# Team_1_board.net
KiCad netlist of a schematic drawn in EAGLE
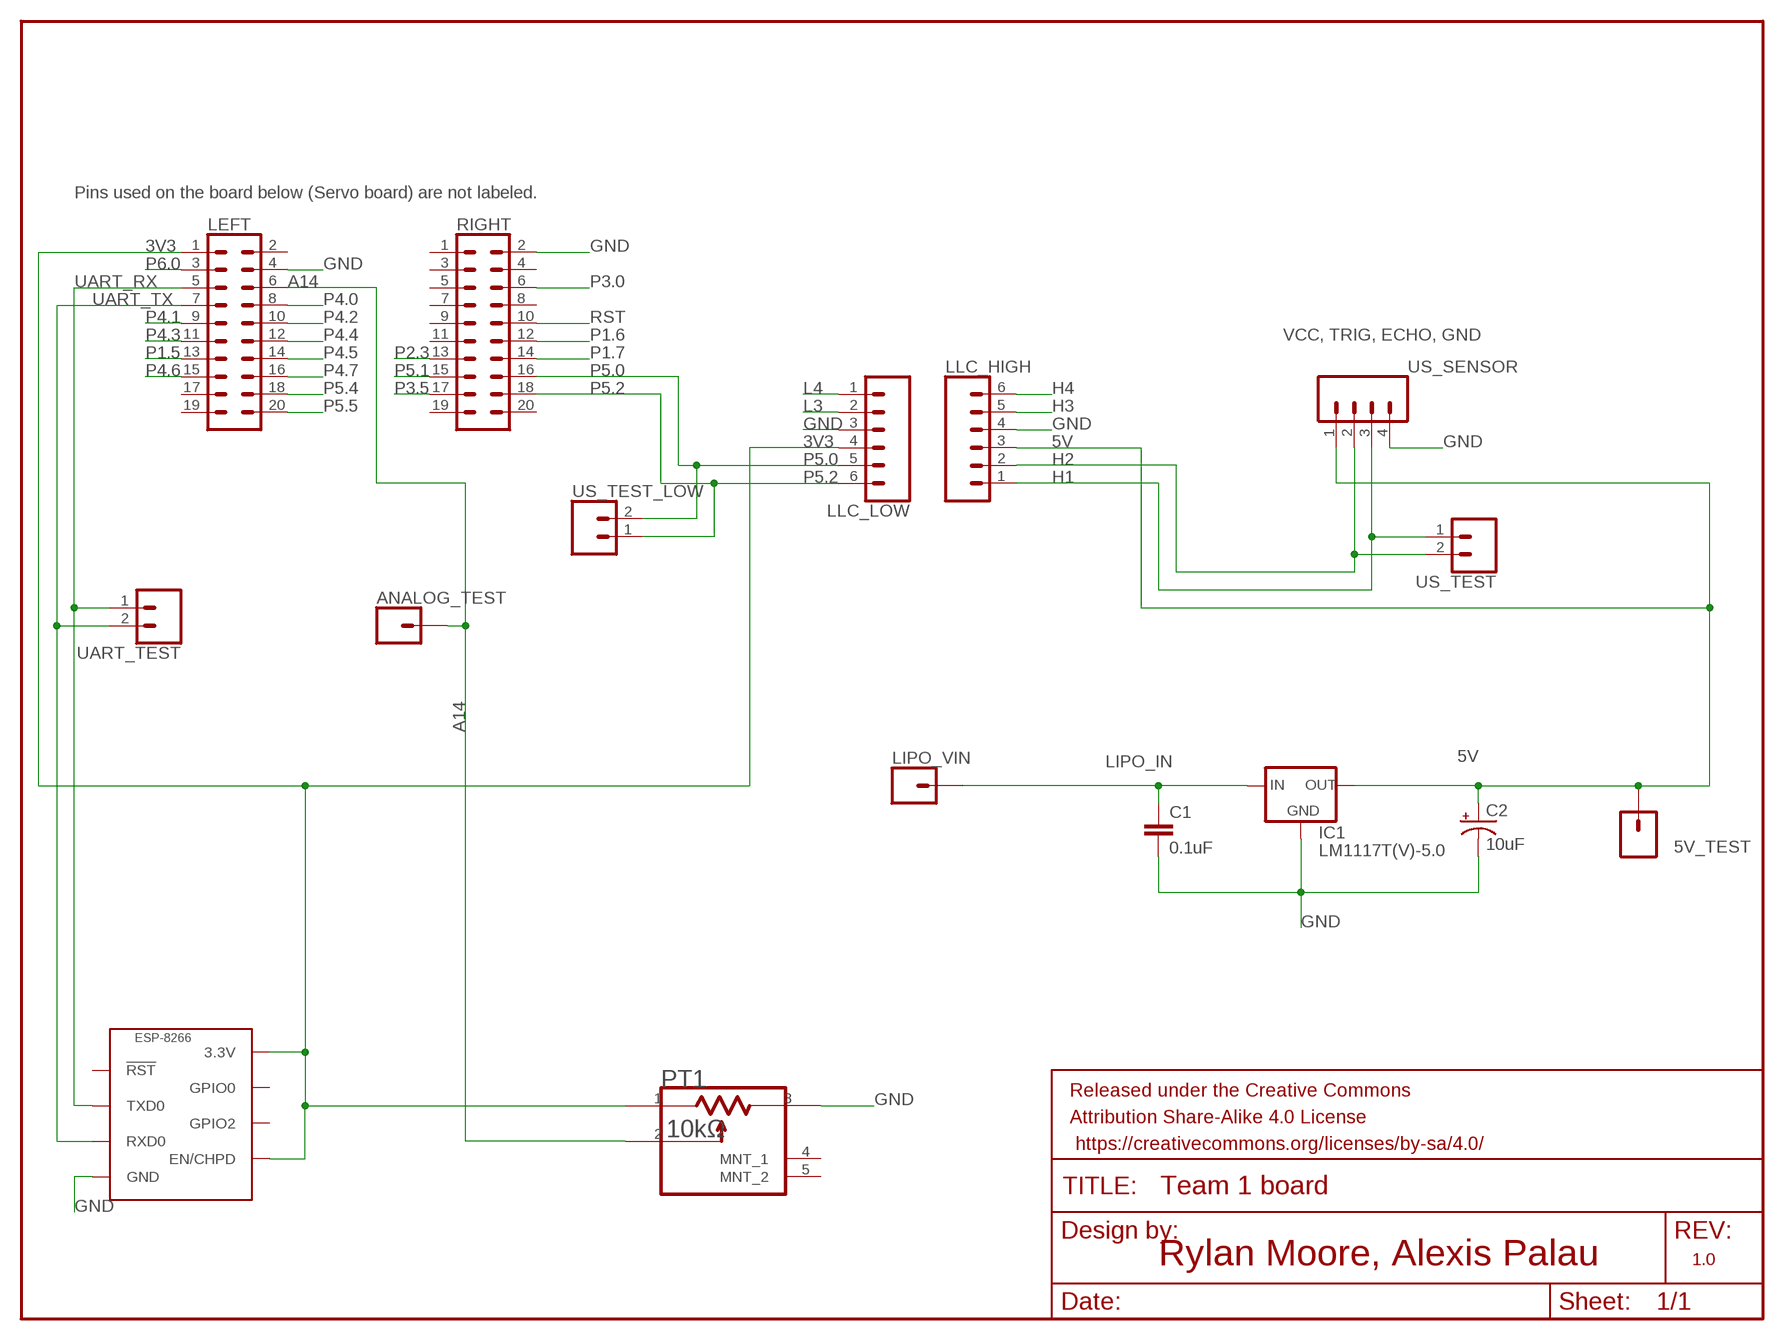
[diagram p0: schematic, sheet 1]

(export (version "E")
  (design (tool "Eeschema 10.0.6"))
  (components
    (comp (ref "5V_TEST")
      (value "CONN_01")
      (footprint "eagle-import:1X01")
      (libsource (lib "eagle-import") (part "CONN_01"))
    )
    (comp (ref "ANALOG_TEST")
      (value "CONN_01")
      (footprint "eagle-import:1X01")
      (libsource (lib "eagle-import") (part "CONN_01"))
    )
    (comp (ref "C1")
      (value "0.1uF")
      (footprint "eagle-import:CAP-PTH-SMALL-KIT")
      (libsource (lib "eagle-import") (part "0.1UF-KIT-EZ-50V-20%"))
    )
    (comp (ref "C2")
      (value "10uF")
      (footprint "eagle-import:CPOL-RADIAL-2.5MM-5MM")
      (libsource (lib "eagle-import") (part "10UF-POLAR-RADIAL-2.5MM-25V-20%"))
    )
    (comp (ref "ESP-8266")
      (value "ESP8266_ESP-01")
      (footprint "eagle-import:ESP8266_ESP-01_NO-SILKSCREEN")
      (libsource (lib "eagle-import") (part "ESP8266_ESP-?01"))
    )
    (comp (ref "FRAME1")
      (value "FRAME-LETTERNO_PACKAGE")
      (footprint "eagle-import:DUMMY")
      (fields (field (name "DESIGNER") "Nobody"))
      (libsource (lib "eagle-import") (part "FRAME-LETTERNO_PACKAGE"))
    )
    (comp (ref "IC1")
      (value "LM1117T(V)-5.0")
      (footprint "eagle-import:TO220V")
      (fields (field (name "MF") "Texas Instruments") (field (name "MPN") "LM1117T-5.0"))
      (libsource (lib "eagle-import") (part "LM1117?-T(V)5.0"))
    )
    (comp (ref "LEFT")
      (value "CONN_10X2NOSILK")
      (footprint "eagle-import:2X10_NOSILK")
      (libsource (lib "eagle-import") (part "CONN_10X2NOSILK"))
    )
    (comp (ref "LIPO_VIN")
      (value "CONN_01")
      (footprint "eagle-import:1X01")
      (libsource (lib "eagle-import") (part "CONN_01"))
    )
    (comp (ref "LLC_HIGH")
      (value "CONN_06SILK_FEMALE_PTH")
      (footprint "eagle-import:1X06")
      (libsource (lib "eagle-import") (part "CONN_06SILK_FEMALE_PTH"))
    )
    (comp (ref "LLC_LOW")
      (value "CONN_06SILK_FEMALE_PTH")
      (footprint "eagle-import:1X06")
      (libsource (lib "eagle-import") (part "CONN_06SILK_FEMALE_PTH"))
    )
    (comp (ref "PT1")
      (value "ECG_EVU-F2AF30B14ECG_EVU-F2AF30B14_0_0")
      (footprint "eagle-import:ECG_EVU-F2AF30B14_0")
      (fields
        (field (name "DIGIKEY_PART_NUMBER") "P3C3103-ND")
        (field (name "MF") "ECG")
        (field (name "MOUSER_PART_NUMBER") "667-EVU-F2AF30B14")
      )
      (libsource (lib "eagle-import") (part "ECG_EVU-F2AF30B14ECG_EVU-F2AF30B14_0_0"))
    )
    (comp (ref "RIGHT")
      (value "CONN_10X2NOSILK")
      (footprint "eagle-import:2X10_NOSILK")
      (libsource (lib "eagle-import") (part "CONN_10X2NOSILK"))
    )
    (comp (ref "UART_TEST")
      (value "CONN_02")
      (footprint "eagle-import:1X02")
      (libsource (lib "eagle-import") (part "CONN_02"))
    )
    (comp (ref "US_SENSOR")
      (value "CONN_04")
      (footprint "eagle-import:1X04")
      (libsource (lib "eagle-import") (part "CONN_04"))
    )
    (comp (ref "US_TEST")
      (value "CONN_02")
      (footprint "eagle-import:1X02")
      (libsource (lib "eagle-import") (part "CONN_02"))
    )
    (comp (ref "US_TEST_LOW")
      (value "CONN_02")
      (footprint "eagle-import:1X02")
      (libsource (lib "eagle-import") (part "CONN_02"))
    )
  )
  (nets
    (net (code "1") (name "/3V3") (class "Default")
      (node (ref "ESP-8266") (pin "3V3") (pinfunction "3.3V_3V3") (pintype "passive"))
      (node (ref "ESP-8266") (pin "EN/CH_PD") (pinfunction "EN/CHPD_EN/CH_PD") (pintype "bidirectional"))
      (node (ref "LEFT") (pin "1") (pinfunction "1_1") (pintype "passive"))
      (node (ref "LLC_LOW") (pin "4") (pinfunction "4_4") (pintype "passive"))
      (node (ref "PT1") (pin "1") (pinfunction "1_1") (pintype "bidirectional"))
    )
    (net (code "2") (name "/5V") (class "Default")
      (node (ref "5V_TEST") (pin "1") (pinfunction "1_1") (pintype "passive"))
      (node (ref "C2") (pin "1") (pinfunction "+_1") (pintype "passive"))
      (node (ref "IC1") (pin "2") (pinfunction "OUT_2") (pintype "passive"))
      (node (ref "LLC_HIGH") (pin "3") (pinfunction "3_3") (pintype "passive"))
      (node (ref "US_SENSOR") (pin "1") (pinfunction "1_1") (pintype "passive"))
    )
    (net (code "3") (name "/A14") (class "Default")
      (node (ref "ANALOG_TEST") (pin "1") (pinfunction "1_1") (pintype "passive"))
      (node (ref "LEFT") (pin "6") (pinfunction "6_6") (pintype "passive"))
      (node (ref "PT1") (pin "2") (pinfunction "2_2") (pintype "bidirectional"))
    )
    (net (code "4") (name "/GND") (class "Default")
      (node (ref "C1") (pin "2") (pinfunction "2_2") (pintype "passive"))
      (node (ref "C2") (pin "2") (pinfunction "-_2") (pintype "passive"))
      (node (ref "ESP-8266") (pin "GND") (pinfunction "GND_GND") (pintype "passive"))
      (node (ref "IC1") (pin "1") (pinfunction "GND_1") (pintype "input"))
      (node (ref "LEFT") (pin "4") (pinfunction "4_4") (pintype "passive"))
      (node (ref "LLC_HIGH") (pin "4") (pinfunction "4_4") (pintype "passive"))
      (node (ref "LLC_LOW") (pin "3") (pinfunction "3_3") (pintype "passive"))
      (node (ref "PT1") (pin "3") (pinfunction "3_3") (pintype "bidirectional"))
      (node (ref "RIGHT") (pin "2") (pinfunction "2_2") (pintype "passive"))
      (node (ref "US_SENSOR") (pin "4") (pinfunction "4_4") (pintype "passive"))
    )
    (net (code "5") (name "/H1") (class "Default")
      (node (ref "LLC_HIGH") (pin "1") (pinfunction "1_1") (pintype "passive"))
      (node (ref "US_SENSOR") (pin "3") (pinfunction "3_3") (pintype "passive"))
      (node (ref "US_TEST") (pin "1") (pinfunction "1_1") (pintype "passive"))
    )
    (net (code "6") (name "/H2") (class "Default")
      (node (ref "LLC_HIGH") (pin "2") (pinfunction "2_2") (pintype "passive"))
      (node (ref "US_SENSOR") (pin "2") (pinfunction "2_2") (pintype "passive"))
      (node (ref "US_TEST") (pin "2") (pinfunction "2_2") (pintype "passive"))
    )
    (net (code "7") (name "/H3") (class "Default")
      (node (ref "LLC_HIGH") (pin "5") (pinfunction "5_5") (pintype "passive"))
    )
    (net (code "8") (name "/H4") (class "Default")
      (node (ref "LLC_HIGH") (pin "6") (pinfunction "6_6") (pintype "passive"))
    )
    (net (code "9") (name "/L3") (class "Default")
      (node (ref "LLC_LOW") (pin "2") (pinfunction "2_2") (pintype "passive"))
    )
    (net (code "10") (name "/L4") (class "Default")
      (node (ref "LLC_LOW") (pin "1") (pinfunction "1_1") (pintype "passive"))
    )
    (net (code "11") (name "/LIPO_IN") (class "Default")
      (node (ref "C1") (pin "1") (pinfunction "1_1") (pintype "passive"))
      (node (ref "IC1") (pin "3") (pinfunction "IN_3") (pintype "input"))
      (node (ref "LIPO_VIN") (pin "1") (pinfunction "1_1") (pintype "passive"))
    )
    (net (code "12") (name "/P1.5") (class "Default")
      (node (ref "LEFT") (pin "13") (pinfunction "13_13") (pintype "passive"))
    )
    (net (code "13") (name "/P1.6") (class "Default")
      (node (ref "RIGHT") (pin "12") (pinfunction "12_12") (pintype "passive"))
    )
    (net (code "14") (name "/P1.7") (class "Default")
      (node (ref "RIGHT") (pin "14") (pinfunction "14_14") (pintype "passive"))
    )
    (net (code "15") (name "/P2.3") (class "Default")
      (node (ref "RIGHT") (pin "13") (pinfunction "13_13") (pintype "passive"))
    )
    (net (code "16") (name "/P3.0") (class "Default")
      (node (ref "RIGHT") (pin "6") (pinfunction "6_6") (pintype "passive"))
    )
    (net (code "17") (name "/P3.5") (class "Default")
      (node (ref "RIGHT") (pin "17") (pinfunction "17_17") (pintype "passive"))
    )
    (net (code "18") (name "/P4.0") (class "Default")
      (node (ref "LEFT") (pin "8") (pinfunction "8_8") (pintype "passive"))
    )
    (net (code "19") (name "/P4.1") (class "Default")
      (node (ref "LEFT") (pin "9") (pinfunction "9_9") (pintype "passive"))
    )
    (net (code "20") (name "/P4.2") (class "Default")
      (node (ref "LEFT") (pin "10") (pinfunction "10_10") (pintype "passive"))
    )
    (net (code "21") (name "/P4.3") (class "Default")
      (node (ref "LEFT") (pin "11") (pinfunction "11_11") (pintype "passive"))
    )
    (net (code "22") (name "/P4.4") (class "Default")
      (node (ref "LEFT") (pin "12") (pinfunction "12_12") (pintype "passive"))
    )
    (net (code "23") (name "/P4.5") (class "Default")
      (node (ref "LEFT") (pin "14") (pinfunction "14_14") (pintype "passive"))
    )
    (net (code "24") (name "/P4.6") (class "Default")
      (node (ref "LEFT") (pin "15") (pinfunction "15_15") (pintype "passive"))
    )
    (net (code "25") (name "/P4.7") (class "Default")
      (node (ref "LEFT") (pin "16") (pinfunction "16_16") (pintype "passive"))
    )
    (net (code "26") (name "/P5.0") (class "Default")
      (node (ref "LLC_LOW") (pin "5") (pinfunction "5_5") (pintype "passive"))
      (node (ref "RIGHT") (pin "16") (pinfunction "16_16") (pintype "passive"))
      (node (ref "US_TEST_LOW") (pin "2") (pinfunction "2_2") (pintype "passive"))
    )
    (net (code "27") (name "/P5.1") (class "Default")
      (node (ref "RIGHT") (pin "15") (pinfunction "15_15") (pintype "passive"))
    )
    (net (code "28") (name "/P5.2") (class "Default")
      (node (ref "LLC_LOW") (pin "6") (pinfunction "6_6") (pintype "passive"))
      (node (ref "RIGHT") (pin "18") (pinfunction "18_18") (pintype "passive"))
      (node (ref "US_TEST_LOW") (pin "1") (pinfunction "1_1") (pintype "passive"))
    )
    (net (code "29") (name "/P5.4") (class "Default")
      (node (ref "LEFT") (pin "18") (pinfunction "18_18") (pintype "passive"))
    )
    (net (code "30") (name "/P5.5") (class "Default")
      (node (ref "LEFT") (pin "20") (pinfunction "20_20") (pintype "passive"))
    )
    (net (code "31") (name "/P6.0") (class "Default")
      (node (ref "LEFT") (pin "3") (pinfunction "3_3") (pintype "passive"))
    )
    (net (code "32") (name "/RST") (class "Default")
      (node (ref "RIGHT") (pin "10") (pinfunction "10_10") (pintype "passive"))
    )
    (net (code "33") (name "/UART_RX") (class "Default")
      (node (ref "ESP-8266") (pin "TX") (pinfunction "TXD0_TX") (pintype "bidirectional"))
      (node (ref "LEFT") (pin "5") (pinfunction "5_5") (pintype "passive"))
      (node (ref "UART_TEST") (pin "1") (pinfunction "1_1") (pintype "passive"))
    )
    (net (code "34") (name "/UART_TX") (class "Default")
      (node (ref "ESP-8266") (pin "RX") (pinfunction "RXD0_RX") (pintype "bidirectional"))
      (node (ref "LEFT") (pin "7") (pinfunction "7_7") (pintype "passive"))
      (node (ref "UART_TEST") (pin "2") (pinfunction "2_2") (pintype "passive"))
    )
    (net (code "35") (name "unconnected-(ESP-8266-PadGPIO0)") (class "Default")
      (node (ref "ESP-8266") (pin "GPIO0") (pinfunction "GPIO0_GPIO0") (pintype "bidirectional"))
    )
    (net (code "36") (name "unconnected-(ESP-8266-PadGPIO2)") (class "Default")
      (node (ref "ESP-8266") (pin "GPIO2") (pinfunction "GPIO2_GPIO2") (pintype "bidirectional"))
    )
    (net (code "37") (name "unconnected-(ESP-8266-~{RST}-PadRST)") (class "Default")
      (node (ref "ESP-8266") (pin "RST") (pinfunction "~{RST}_RST") (pintype "bidirectional"))
    )
    (net (code "38") (name "unconnected-(LEFT-Pad2)") (class "Default")
      (node (ref "LEFT") (pin "2") (pinfunction "2_2") (pintype "passive"))
    )
    (net (code "39") (name "unconnected-(LEFT-Pad17)") (class "Default")
      (node (ref "LEFT") (pin "17") (pinfunction "17_17") (pintype "passive"))
    )
    (net (code "40") (name "unconnected-(LEFT-Pad19)") (class "Default")
      (node (ref "LEFT") (pin "19") (pinfunction "19_19") (pintype "passive"))
    )
    (net (code "41") (name "unconnected-(PT1-MNT_1-Pad4)") (class "Default")
      (node (ref "PT1") (pin "4") (pinfunction "MNT_1_4") (pintype "bidirectional"))
    )
    (net (code "42") (name "unconnected-(PT1-MNT_2-Pad5)") (class "Default")
      (node (ref "PT1") (pin "5") (pinfunction "MNT_2_5") (pintype "bidirectional"))
    )
    (net (code "43") (name "unconnected-(RIGHT-Pad1)") (class "Default")
      (node (ref "RIGHT") (pin "1") (pinfunction "1_1") (pintype "passive"))
    )
    (net (code "44") (name "unconnected-(RIGHT-Pad3)") (class "Default")
      (node (ref "RIGHT") (pin "3") (pinfunction "3_3") (pintype "passive"))
    )
    (net (code "45") (name "unconnected-(RIGHT-Pad4)") (class "Default")
      (node (ref "RIGHT") (pin "4") (pinfunction "4_4") (pintype "passive"))
    )
    (net (code "46") (name "unconnected-(RIGHT-Pad5)") (class "Default")
      (node (ref "RIGHT") (pin "5") (pinfunction "5_5") (pintype "passive"))
    )
    (net (code "47") (name "unconnected-(RIGHT-Pad7)") (class "Default")
      (node (ref "RIGHT") (pin "7") (pinfunction "7_7") (pintype "passive"))
    )
    (net (code "48") (name "unconnected-(RIGHT-Pad8)") (class "Default")
      (node (ref "RIGHT") (pin "8") (pinfunction "8_8") (pintype "passive"))
    )
    (net (code "49") (name "unconnected-(RIGHT-Pad9)") (class "Default")
      (node (ref "RIGHT") (pin "9") (pinfunction "9_9") (pintype "passive"))
    )
    (net (code "50") (name "unconnected-(RIGHT-Pad11)") (class "Default")
      (node (ref "RIGHT") (pin "11") (pinfunction "11_11") (pintype "passive"))
    )
    (net (code "51") (name "unconnected-(RIGHT-Pad19)") (class "Default")
      (node (ref "RIGHT") (pin "19") (pinfunction "19_19") (pintype "passive"))
    )
    (net (code "52") (name "unconnected-(RIGHT-Pad20)") (class "Default")
      (node (ref "RIGHT") (pin "20") (pinfunction "20_20") (pintype "passive"))
    )
  )
)
